# DragonBall.net
KiCad netlist of a schematic drawn in EAGLE
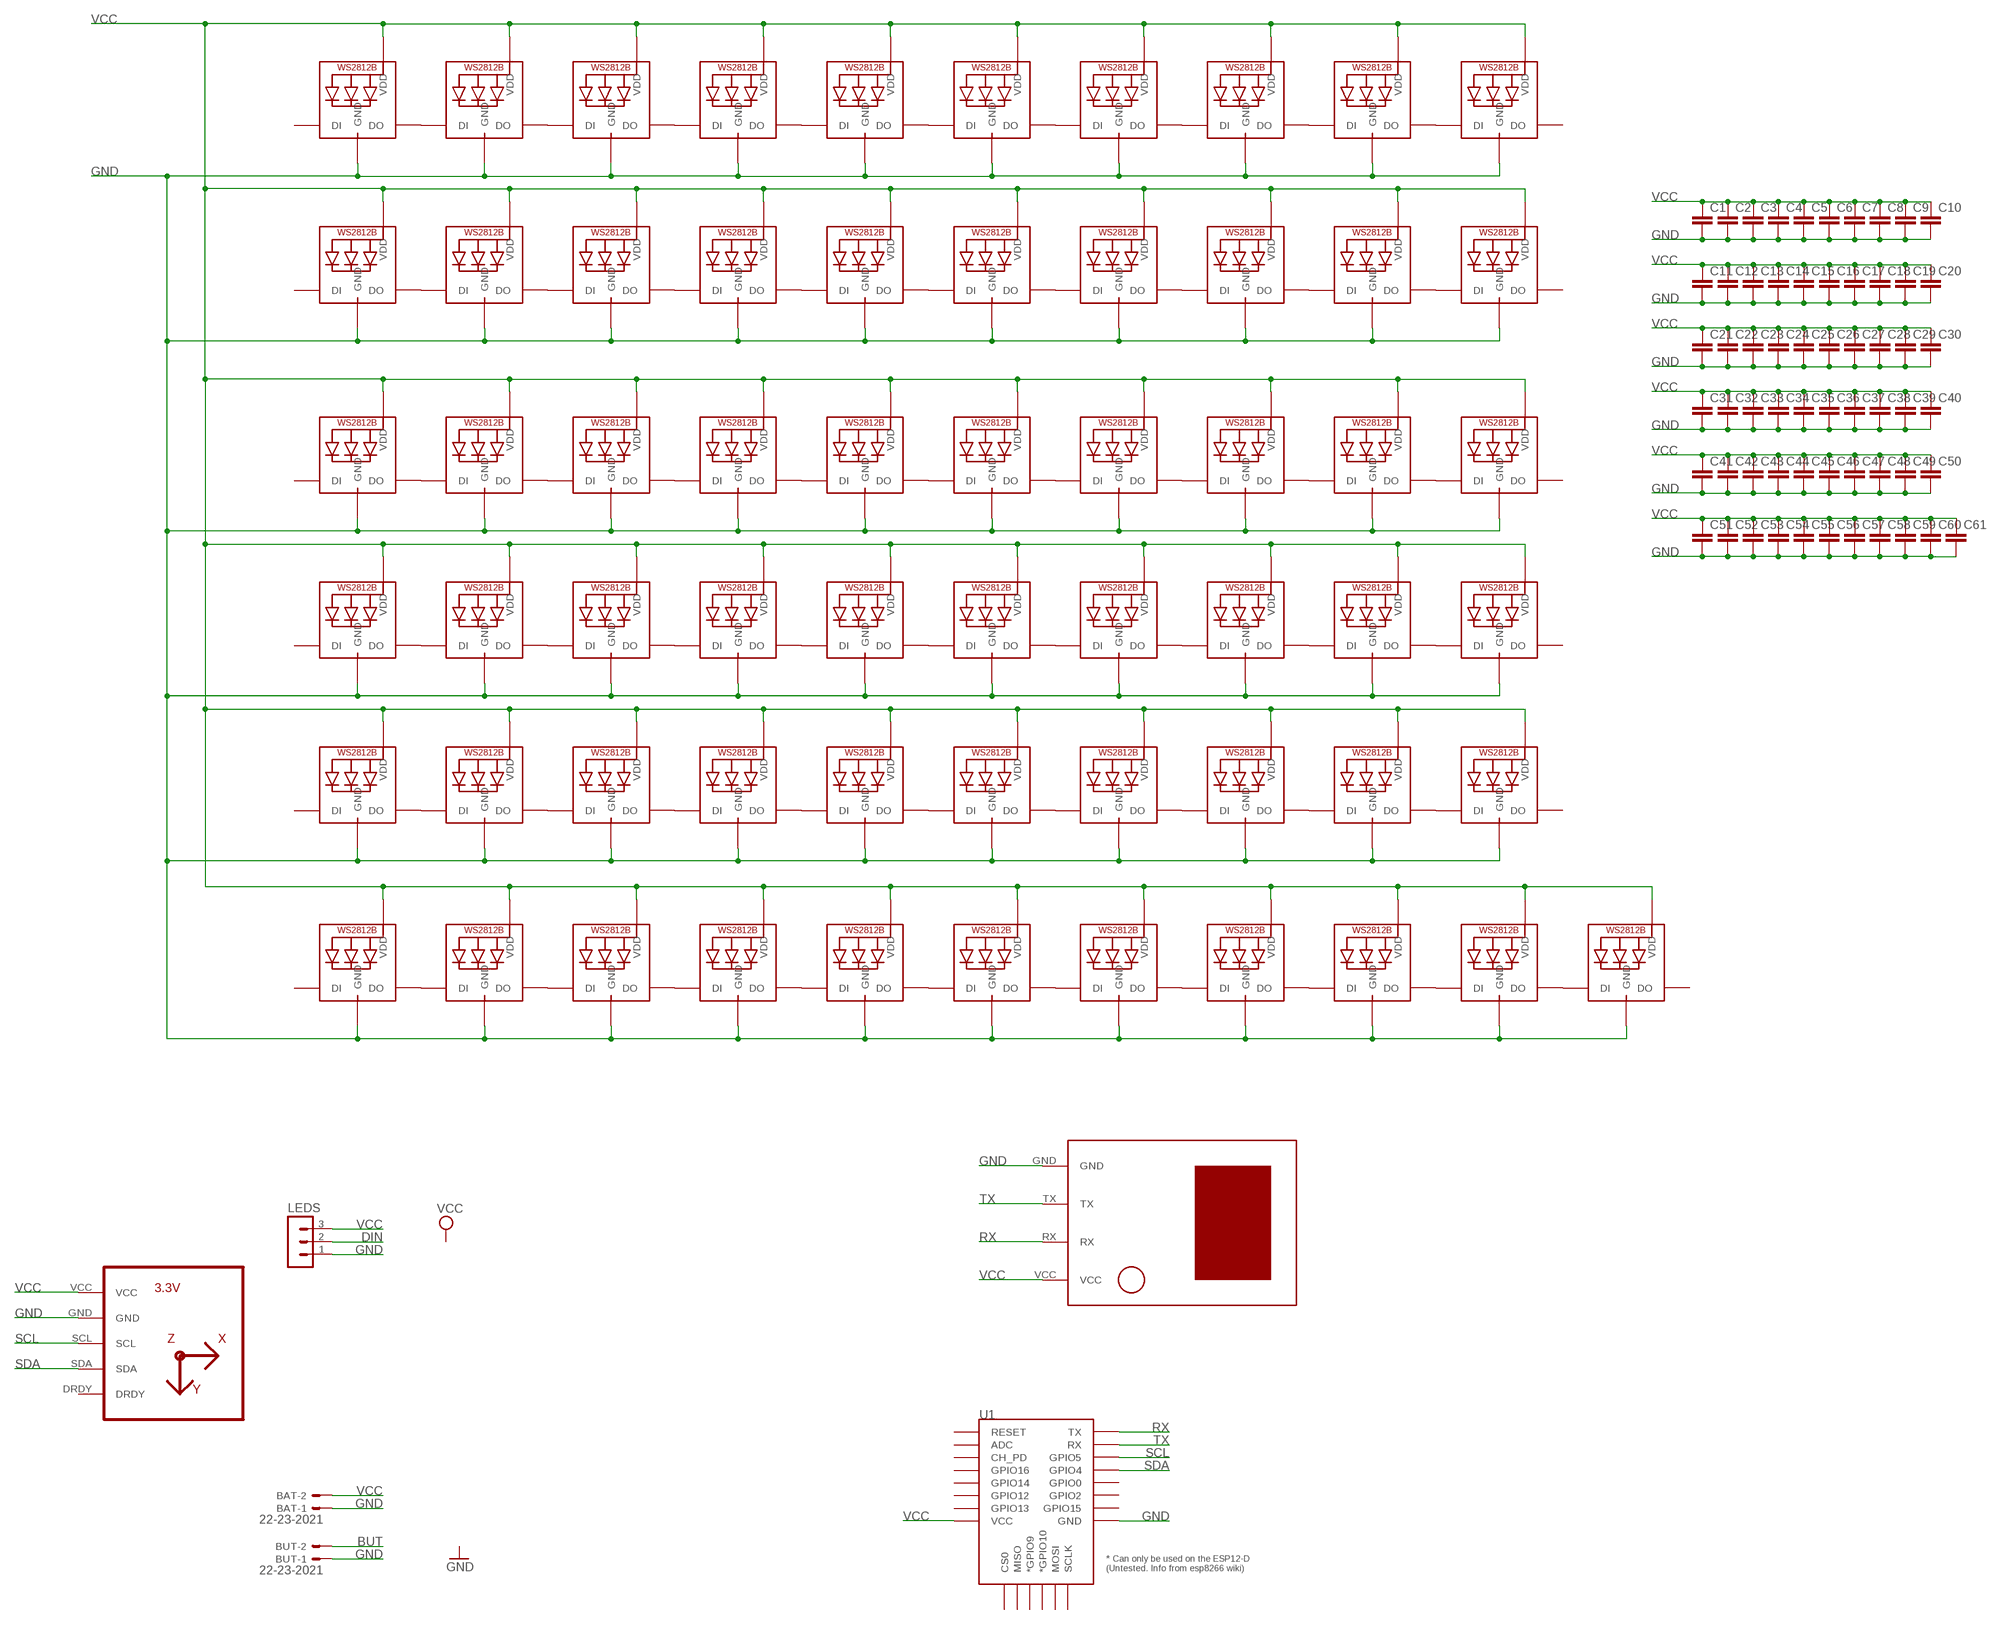
[diagram p0: schematic, sheet 1]

(export (version "E")
  (design (tool "Eeschema 10.0.6"))
  (components
    (comp (ref "BAT")
      (value "22-23-2021")
      (footprint "eagle-import:22-23-2021")
      (fields (field (name "MF") "MOLEX"))
      (libsource (lib "eagle-import") (part "22-23-2021"))
    )
    (comp (ref "BUT")
      (value "22-23-2021")
      (footprint "eagle-import:22-23-2021")
      (fields (field (name "MF") "MOLEX"))
      (libsource (lib "eagle-import") (part "22-23-2021"))
    )
    (comp (ref "C1")
      (value "C-EUC0402K")
      (footprint "eagle-import:C0402K")
      (libsource (lib "eagle-import") (part "C-EUC0402K"))
    )
    (comp (ref "C2")
      (value "C-EUC0402K")
      (footprint "eagle-import:C0402K")
      (libsource (lib "eagle-import") (part "C-EUC0402K"))
    )
    (comp (ref "C3")
      (value "C-EUC0402K")
      (footprint "eagle-import:C0402K")
      (libsource (lib "eagle-import") (part "C-EUC0402K"))
    )
    (comp (ref "C4")
      (value "C-EUC0402K")
      (footprint "eagle-import:C0402K")
      (libsource (lib "eagle-import") (part "C-EUC0402K"))
    )
    (comp (ref "C5")
      (value "C-EUC0402K")
      (footprint "eagle-import:C0402K")
      (libsource (lib "eagle-import") (part "C-EUC0402K"))
    )
    (comp (ref "C6")
      (value "C-EUC0402K")
      (footprint "eagle-import:C0402K")
      (libsource (lib "eagle-import") (part "C-EUC0402K"))
    )
    (comp (ref "C7")
      (value "C-EUC0402K")
      (footprint "eagle-import:C0402K")
      (libsource (lib "eagle-import") (part "C-EUC0402K"))
    )
    (comp (ref "C8")
      (value "C-EUC0402K")
      (footprint "eagle-import:C0402K")
      (libsource (lib "eagle-import") (part "C-EUC0402K"))
    )
    (comp (ref "C9")
      (value "C-EUC0402K")
      (footprint "eagle-import:C0402K")
      (libsource (lib "eagle-import") (part "C-EUC0402K"))
    )
    (comp (ref "C10")
      (value "C-EUC0402K")
      (footprint "eagle-import:C0402K")
      (libsource (lib "eagle-import") (part "C-EUC0402K"))
    )
    (comp (ref "C11")
      (value "C-EUC0402K")
      (footprint "eagle-import:C0402K")
      (libsource (lib "eagle-import") (part "C-EUC0402K"))
    )
    (comp (ref "C12")
      (value "C-EUC0402K")
      (footprint "eagle-import:C0402K")
      (libsource (lib "eagle-import") (part "C-EUC0402K"))
    )
    (comp (ref "C13")
      (value "C-EUC0402K")
      (footprint "eagle-import:C0402K")
      (libsource (lib "eagle-import") (part "C-EUC0402K"))
    )
    (comp (ref "C14")
      (value "C-EUC0402K")
      (footprint "eagle-import:C0402K")
      (libsource (lib "eagle-import") (part "C-EUC0402K"))
    )
    (comp (ref "C15")
      (value "C-EUC0402K")
      (footprint "eagle-import:C0402K")
      (libsource (lib "eagle-import") (part "C-EUC0402K"))
    )
    (comp (ref "C16")
      (value "C-EUC0402K")
      (footprint "eagle-import:C0402K")
      (libsource (lib "eagle-import") (part "C-EUC0402K"))
    )
    (comp (ref "C17")
      (value "C-EUC0402K")
      (footprint "eagle-import:C0402K")
      (libsource (lib "eagle-import") (part "C-EUC0402K"))
    )
    (comp (ref "C18")
      (value "C-EUC0402K")
      (footprint "eagle-import:C0402K")
      (libsource (lib "eagle-import") (part "C-EUC0402K"))
    )
    (comp (ref "C19")
      (value "C-EUC0402K")
      (footprint "eagle-import:C0402K")
      (libsource (lib "eagle-import") (part "C-EUC0402K"))
    )
    (comp (ref "C20")
      (value "C-EUC0402K")
      (footprint "eagle-import:C0402K")
      (libsource (lib "eagle-import") (part "C-EUC0402K"))
    )
    (comp (ref "C21")
      (value "C-EUC0402K")
      (footprint "eagle-import:C0402K")
      (libsource (lib "eagle-import") (part "C-EUC0402K"))
    )
    (comp (ref "C22")
      (value "C-EUC0402K")
      (footprint "eagle-import:C0402K")
      (libsource (lib "eagle-import") (part "C-EUC0402K"))
    )
    (comp (ref "C23")
      (value "C-EUC0402K")
      (footprint "eagle-import:C0402K")
      (libsource (lib "eagle-import") (part "C-EUC0402K"))
    )
    (comp (ref "C24")
      (value "C-EUC0402K")
      (footprint "eagle-import:C0402K")
      (libsource (lib "eagle-import") (part "C-EUC0402K"))
    )
    (comp (ref "C25")
      (value "C-EUC0402K")
      (footprint "eagle-import:C0402K")
      (libsource (lib "eagle-import") (part "C-EUC0402K"))
    )
    (comp (ref "C26")
      (value "C-EUC0402K")
      (footprint "eagle-import:C0402K")
      (libsource (lib "eagle-import") (part "C-EUC0402K"))
    )
    (comp (ref "C27")
      (value "C-EUC0402K")
      (footprint "eagle-import:C0402K")
      (libsource (lib "eagle-import") (part "C-EUC0402K"))
    )
    (comp (ref "C28")
      (value "C-EUC0402K")
      (footprint "eagle-import:C0402K")
      (libsource (lib "eagle-import") (part "C-EUC0402K"))
    )
    (comp (ref "C29")
      (value "C-EUC0402K")
      (footprint "eagle-import:C0402K")
      (libsource (lib "eagle-import") (part "C-EUC0402K"))
    )
    (comp (ref "C30")
      (value "C-EUC0402K")
      (footprint "eagle-import:C0402K")
      (libsource (lib "eagle-import") (part "C-EUC0402K"))
    )
    (comp (ref "C31")
      (value "C-EUC0402K")
      (footprint "eagle-import:C0402K")
      (libsource (lib "eagle-import") (part "C-EUC0402K"))
    )
    (comp (ref "C32")
      (value "C-EUC0402K")
      (footprint "eagle-import:C0402K")
      (libsource (lib "eagle-import") (part "C-EUC0402K"))
    )
    (comp (ref "C33")
      (value "C-EUC0402K")
      (footprint "eagle-import:C0402K")
      (libsource (lib "eagle-import") (part "C-EUC0402K"))
    )
    (comp (ref "C34")
      (value "C-EUC0402K")
      (footprint "eagle-import:C0402K")
      (libsource (lib "eagle-import") (part "C-EUC0402K"))
    )
    (comp (ref "C35")
      (value "C-EUC0402K")
      (footprint "eagle-import:C0402K")
      (libsource (lib "eagle-import") (part "C-EUC0402K"))
    )
    (comp (ref "C36")
      (value "C-EUC0402K")
      (footprint "eagle-import:C0402K")
      (libsource (lib "eagle-import") (part "C-EUC0402K"))
    )
    (comp (ref "C37")
      (value "C-EUC0402K")
      (footprint "eagle-import:C0402K")
      (libsource (lib "eagle-import") (part "C-EUC0402K"))
    )
    (comp (ref "C38")
      (value "C-EUC0402K")
      (footprint "eagle-import:C0402K")
      (libsource (lib "eagle-import") (part "C-EUC0402K"))
    )
    (comp (ref "C39")
      (value "C-EUC0402K")
      (footprint "eagle-import:C0402K")
      (libsource (lib "eagle-import") (part "C-EUC0402K"))
    )
    (comp (ref "C40")
      (value "C-EUC0402K")
      (footprint "eagle-import:C0402K")
      (libsource (lib "eagle-import") (part "C-EUC0402K"))
    )
    (comp (ref "C41")
      (value "C-EUC0402K")
      (footprint "eagle-import:C0402K")
      (libsource (lib "eagle-import") (part "C-EUC0402K"))
    )
    (comp (ref "C42")
      (value "C-EUC0402K")
      (footprint "eagle-import:C0402K")
      (libsource (lib "eagle-import") (part "C-EUC0402K"))
    )
    (comp (ref "C43")
      (value "C-EUC0402K")
      (footprint "eagle-import:C0402K")
      (libsource (lib "eagle-import") (part "C-EUC0402K"))
    )
    (comp (ref "C44")
      (value "C-EUC0402K")
      (footprint "eagle-import:C0402K")
      (libsource (lib "eagle-import") (part "C-EUC0402K"))
    )
    (comp (ref "C45")
      (value "C-EUC0402K")
      (footprint "eagle-import:C0402K")
      (libsource (lib "eagle-import") (part "C-EUC0402K"))
    )
    (comp (ref "C46")
      (value "C-EUC0402K")
      (footprint "eagle-import:C0402K")
      (libsource (lib "eagle-import") (part "C-EUC0402K"))
    )
    (comp (ref "C47")
      (value "C-EUC0402K")
      (footprint "eagle-import:C0402K")
      (libsource (lib "eagle-import") (part "C-EUC0402K"))
    )
    (comp (ref "C48")
      (value "C-EUC0402K")
      (footprint "eagle-import:C0402K")
      (libsource (lib "eagle-import") (part "C-EUC0402K"))
    )
    (comp (ref "C49")
      (value "C-EUC0402K")
      (footprint "eagle-import:C0402K")
      (libsource (lib "eagle-import") (part "C-EUC0402K"))
    )
    (comp (ref "C50")
      (value "C-EUC0402K")
      (footprint "eagle-import:C0402K")
      (libsource (lib "eagle-import") (part "C-EUC0402K"))
    )
    (comp (ref "C51")
      (value "C-EUC0402K")
      (footprint "eagle-import:C0402K")
      (libsource (lib "eagle-import") (part "C-EUC0402K"))
    )
    (comp (ref "C52")
      (value "C-EUC0402K")
      (footprint "eagle-import:C0402K")
      (libsource (lib "eagle-import") (part "C-EUC0402K"))
    )
    (comp (ref "C53")
      (value "C-EUC0402K")
      (footprint "eagle-import:C0402K")
      (libsource (lib "eagle-import") (part "C-EUC0402K"))
    )
    (comp (ref "C54")
      (value "C-EUC0402K")
      (footprint "eagle-import:C0402K")
      (libsource (lib "eagle-import") (part "C-EUC0402K"))
    )
    (comp (ref "C55")
      (value "C-EUC0402K")
      (footprint "eagle-import:C0402K")
      (libsource (lib "eagle-import") (part "C-EUC0402K"))
    )
    (comp (ref "C56")
      (value "C-EUC0402K")
      (footprint "eagle-import:C0402K")
      (libsource (lib "eagle-import") (part "C-EUC0402K"))
    )
    (comp (ref "C57")
      (value "C-EUC0402K")
      (footprint "eagle-import:C0402K")
      (libsource (lib "eagle-import") (part "C-EUC0402K"))
    )
    (comp (ref "C58")
      (value "C-EUC0402K")
      (footprint "eagle-import:C0402K")
      (libsource (lib "eagle-import") (part "C-EUC0402K"))
    )
    (comp (ref "C59")
      (value "C-EUC0402K")
      (footprint "eagle-import:C0402K")
      (libsource (lib "eagle-import") (part "C-EUC0402K"))
    )
    (comp (ref "C60")
      (value "C-EUC0402K")
      (footprint "eagle-import:C0402K")
      (libsource (lib "eagle-import") (part "C-EUC0402K"))
    )
    (comp (ref "C61")
      (value "C-EUC0402K")
      (footprint "eagle-import:C0402K")
      (libsource (lib "eagle-import") (part "C-EUC0402K"))
    )
    (comp (ref "GYRO")
      (value "HMC5883LGY-271")
      (footprint "eagle-import:GY-271")
      (libsource (lib "eagle-import") (part "HMC5883LGY-271"))
    )
    (comp (ref "LED1")
      (value "WS2812B_5050N")
      (footprint "eagle-import:WS2812B-NARROW")
      (libsource (lib "eagle-import") (part "WS2812B_5050N"))
    )
    (comp (ref "LED2")
      (value "WS2812B_5050N")
      (footprint "eagle-import:WS2812B-NARROW")
      (libsource (lib "eagle-import") (part "WS2812B_5050N"))
    )
    (comp (ref "LED3")
      (value "WS2812B_5050N")
      (footprint "eagle-import:WS2812B-NARROW")
      (libsource (lib "eagle-import") (part "WS2812B_5050N"))
    )
    (comp (ref "LED4")
      (value "WS2812B_5050N")
      (footprint "eagle-import:WS2812B-NARROW")
      (libsource (lib "eagle-import") (part "WS2812B_5050N"))
    )
    (comp (ref "LED5")
      (value "WS2812B_5050N")
      (footprint "eagle-import:WS2812B-NARROW")
      (libsource (lib "eagle-import") (part "WS2812B_5050N"))
    )
    (comp (ref "LED6")
      (value "WS2812B_5050N")
      (footprint "eagle-import:WS2812B-NARROW")
      (libsource (lib "eagle-import") (part "WS2812B_5050N"))
    )
    (comp (ref "LED7")
      (value "WS2812B_5050N")
      (footprint "eagle-import:WS2812B-NARROW")
      (libsource (lib "eagle-import") (part "WS2812B_5050N"))
    )
    (comp (ref "LED8")
      (value "WS2812B_5050N")
      (footprint "eagle-import:WS2812B-NARROW")
      (libsource (lib "eagle-import") (part "WS2812B_5050N"))
    )
    (comp (ref "LED9")
      (value "WS2812B_5050N")
      (footprint "eagle-import:WS2812B-NARROW")
      (libsource (lib "eagle-import") (part "WS2812B_5050N"))
    )
    (comp (ref "LED10")
      (value "WS2812B_5050N")
      (footprint "eagle-import:WS2812B-NARROW")
      (libsource (lib "eagle-import") (part "WS2812B_5050N"))
    )
    (comp (ref "LED11")
      (value "WS2812B_5050N")
      (footprint "eagle-import:WS2812B-NARROW")
      (libsource (lib "eagle-import") (part "WS2812B_5050N"))
    )
    (comp (ref "LED12")
      (value "WS2812B_5050N")
      (footprint "eagle-import:WS2812B-NARROW")
      (libsource (lib "eagle-import") (part "WS2812B_5050N"))
    )
    (comp (ref "LED13")
      (value "WS2812B_5050N")
      (footprint "eagle-import:WS2812B-NARROW")
      (libsource (lib "eagle-import") (part "WS2812B_5050N"))
    )
    (comp (ref "LED14")
      (value "WS2812B_5050N")
      (footprint "eagle-import:WS2812B-NARROW")
      (libsource (lib "eagle-import") (part "WS2812B_5050N"))
    )
    (comp (ref "LED15")
      (value "WS2812B_5050N")
      (footprint "eagle-import:WS2812B-NARROW")
      (libsource (lib "eagle-import") (part "WS2812B_5050N"))
    )
    (comp (ref "LED16")
      (value "WS2812B_5050N")
      (footprint "eagle-import:WS2812B-NARROW")
      (libsource (lib "eagle-import") (part "WS2812B_5050N"))
    )
    (comp (ref "LED17")
      (value "WS2812B_5050N")
      (footprint "eagle-import:WS2812B-NARROW")
      (libsource (lib "eagle-import") (part "WS2812B_5050N"))
    )
    (comp (ref "LED18")
      (value "WS2812B_5050N")
      (footprint "eagle-import:WS2812B-NARROW")
      (libsource (lib "eagle-import") (part "WS2812B_5050N"))
    )
    (comp (ref "LED19")
      (value "WS2812B_5050N")
      (footprint "eagle-import:WS2812B-NARROW")
      (libsource (lib "eagle-import") (part "WS2812B_5050N"))
    )
    (comp (ref "LED20")
      (value "WS2812B_5050N")
      (footprint "eagle-import:WS2812B-NARROW")
      (libsource (lib "eagle-import") (part "WS2812B_5050N"))
    )
    (comp (ref "LED21")
      (value "WS2812B_5050N")
      (footprint "eagle-import:WS2812B-NARROW")
      (libsource (lib "eagle-import") (part "WS2812B_5050N"))
    )
    (comp (ref "LED22")
      (value "WS2812B_5050N")
      (footprint "eagle-import:WS2812B-NARROW")
      (libsource (lib "eagle-import") (part "WS2812B_5050N"))
    )
    (comp (ref "LED23")
      (value "WS2812B_5050N")
      (footprint "eagle-import:WS2812B-NARROW")
      (libsource (lib "eagle-import") (part "WS2812B_5050N"))
    )
    (comp (ref "LED24")
      (value "WS2812B_5050N")
      (footprint "eagle-import:WS2812B-NARROW")
      (libsource (lib "eagle-import") (part "WS2812B_5050N"))
    )
    (comp (ref "LED25")
      (value "WS2812B_5050N")
      (footprint "eagle-import:WS2812B-NARROW")
      (libsource (lib "eagle-import") (part "WS2812B_5050N"))
    )
    (comp (ref "LED26")
      (value "WS2812B_5050N")
      (footprint "eagle-import:WS2812B-NARROW")
      (libsource (lib "eagle-import") (part "WS2812B_5050N"))
    )
    (comp (ref "LED27")
      (value "WS2812B_5050N")
      (footprint "eagle-import:WS2812B-NARROW")
      (libsource (lib "eagle-import") (part "WS2812B_5050N"))
    )
    (comp (ref "LED28")
      (value "WS2812B_5050N")
      (footprint "eagle-import:WS2812B-NARROW")
      (libsource (lib "eagle-import") (part "WS2812B_5050N"))
    )
    (comp (ref "LED29")
      (value "WS2812B_5050N")
      (footprint "eagle-import:WS2812B-NARROW")
      (libsource (lib "eagle-import") (part "WS2812B_5050N"))
    )
    (comp (ref "LED30")
      (value "WS2812B_5050N")
      (footprint "eagle-import:WS2812B-NARROW")
      (libsource (lib "eagle-import") (part "WS2812B_5050N"))
    )
    (comp (ref "LED31")
      (value "WS2812B_5050N")
      (footprint "eagle-import:WS2812B-NARROW")
      (libsource (lib "eagle-import") (part "WS2812B_5050N"))
    )
    (comp (ref "LED32")
      (value "WS2812B_5050N")
      (footprint "eagle-import:WS2812B-NARROW")
      (libsource (lib "eagle-import") (part "WS2812B_5050N"))
    )
    (comp (ref "LED33")
      (value "WS2812B_5050N")
      (footprint "eagle-import:WS2812B-NARROW")
      (libsource (lib "eagle-import") (part "WS2812B_5050N"))
    )
    (comp (ref "LED34")
      (value "WS2812B_5050N")
      (footprint "eagle-import:WS2812B-NARROW")
      (libsource (lib "eagle-import") (part "WS2812B_5050N"))
    )
    (comp (ref "LED35")
      (value "WS2812B_5050N")
      (footprint "eagle-import:WS2812B-NARROW")
      (libsource (lib "eagle-import") (part "WS2812B_5050N"))
    )
    (comp (ref "LED36")
      (value "WS2812B_5050N")
      (footprint "eagle-import:WS2812B-NARROW")
      (libsource (lib "eagle-import") (part "WS2812B_5050N"))
    )
    (comp (ref "LED37")
      (value "WS2812B_5050N")
      (footprint "eagle-import:WS2812B-NARROW")
      (libsource (lib "eagle-import") (part "WS2812B_5050N"))
    )
    (comp (ref "LED38")
      (value "WS2812B_5050N")
      (footprint "eagle-import:WS2812B-NARROW")
      (libsource (lib "eagle-import") (part "WS2812B_5050N"))
    )
    (comp (ref "LED39")
      (value "WS2812B_5050N")
      (footprint "eagle-import:WS2812B-NARROW")
      (libsource (lib "eagle-import") (part "WS2812B_5050N"))
    )
    (comp (ref "LED40")
      (value "WS2812B_5050N")
      (footprint "eagle-import:WS2812B-NARROW")
      (libsource (lib "eagle-import") (part "WS2812B_5050N"))
    )
    (comp (ref "LED41")
      (value "WS2812B_5050N")
      (footprint "eagle-import:WS2812B-NARROW")
      (libsource (lib "eagle-import") (part "WS2812B_5050N"))
    )
    (comp (ref "LED42")
      (value "WS2812B_5050N")
      (footprint "eagle-import:WS2812B-NARROW")
      (libsource (lib "eagle-import") (part "WS2812B_5050N"))
    )
    (comp (ref "LED43")
      (value "WS2812B_5050N")
      (footprint "eagle-import:WS2812B-NARROW")
      (libsource (lib "eagle-import") (part "WS2812B_5050N"))
    )
    (comp (ref "LED44")
      (value "WS2812B_5050N")
      (footprint "eagle-import:WS2812B-NARROW")
      (libsource (lib "eagle-import") (part "WS2812B_5050N"))
    )
    (comp (ref "LED45")
      (value "WS2812B_5050N")
      (footprint "eagle-import:WS2812B-NARROW")
      (libsource (lib "eagle-import") (part "WS2812B_5050N"))
    )
    (comp (ref "LED46")
      (value "WS2812B_5050N")
      (footprint "eagle-import:WS2812B-NARROW")
      (libsource (lib "eagle-import") (part "WS2812B_5050N"))
    )
    (comp (ref "LED47")
      (value "WS2812B_5050N")
      (footprint "eagle-import:WS2812B-NARROW")
      (libsource (lib "eagle-import") (part "WS2812B_5050N"))
    )
    (comp (ref "LED48")
      (value "WS2812B_5050N")
      (footprint "eagle-import:WS2812B-NARROW")
      (libsource (lib "eagle-import") (part "WS2812B_5050N"))
    )
    (comp (ref "LED49")
      (value "WS2812B_5050N")
      (footprint "eagle-import:WS2812B-NARROW")
      (libsource (lib "eagle-import") (part "WS2812B_5050N"))
    )
    (comp (ref "LED50")
      (value "WS2812B_5050N")
      (footprint "eagle-import:WS2812B-NARROW")
      (libsource (lib "eagle-import") (part "WS2812B_5050N"))
    )
    (comp (ref "LED51")
      (value "WS2812B_5050N")
      (footprint "eagle-import:WS2812B-NARROW")
      (libsource (lib "eagle-import") (part "WS2812B_5050N"))
    )
    (comp (ref "LED52")
      (value "WS2812B_5050N")
      (footprint "eagle-import:WS2812B-NARROW")
      (libsource (lib "eagle-import") (part "WS2812B_5050N"))
    )
    (comp (ref "LED53")
      (value "WS2812B_5050N")
      (footprint "eagle-import:WS2812B-NARROW")
      (libsource (lib "eagle-import") (part "WS2812B_5050N"))
    )
    (comp (ref "LED54")
      (value "WS2812B_5050N")
      (footprint "eagle-import:WS2812B-NARROW")
      (libsource (lib "eagle-import") (part "WS2812B_5050N"))
    )
    (comp (ref "LED55")
      (value "WS2812B_5050N")
      (footprint "eagle-import:WS2812B-NARROW")
      (libsource (lib "eagle-import") (part "WS2812B_5050N"))
    )
    (comp (ref "LED56")
      (value "WS2812B_5050N")
      (footprint "eagle-import:WS2812B-NARROW")
      (libsource (lib "eagle-import") (part "WS2812B_5050N"))
    )
    (comp (ref "LED57")
      (value "WS2812B_5050N")
      (footprint "eagle-import:WS2812B-NARROW")
      (libsource (lib "eagle-import") (part "WS2812B_5050N"))
    )
    (comp (ref "LED58")
      (value "WS2812B_5050N")
      (footprint "eagle-import:WS2812B-NARROW")
      (libsource (lib "eagle-import") (part "WS2812B_5050N"))
    )
    (comp (ref "LED59")
      (value "WS2812B_5050N")
      (footprint "eagle-import:WS2812B-NARROW")
      (libsource (lib "eagle-import") (part "WS2812B_5050N"))
    )
    (comp (ref "LED60")
      (value "WS2812B_5050N")
      (footprint "eagle-import:WS2812B-NARROW")
      (libsource (lib "eagle-import") (part "WS2812B_5050N"))
    )
    (comp (ref "LED61")
      (value "WS2812B_5050N")
      (footprint "eagle-import:WS2812B-NARROW")
      (libsource (lib "eagle-import") (part "WS2812B_5050N"))
    )
    (comp (ref "LEDS")
      (value "MA03-1")
      (footprint "eagle-import:MA03-1")
      (libsource (lib "eagle-import") (part "MA03-1"))
    )
    (comp (ref "U$3")
      (value "U-BLOX-NEO6V2")
      (footprint "eagle-import:U-BLOX-NEO6V2")
      (libsource (lib "eagle-import") (part "U-BLOX-NEO6V2"))
    )
    (comp (ref "U1")
      (value "ESP12ESMD")
      (footprint "eagle-import:ESP12E-SMD")
      (libsource (lib "eagle-import") (part "ESP12ESMD"))
    )
  )
  (nets
    (net (code "1") (name "/BUT") (class "Default")
      (node (ref "BUT") (pin "2") (pinfunction "S_2") (pintype "passive"))
    )
    (net (code "2") (name "/DIN") (class "Default")
      (node (ref "LEDS") (pin "2") (pinfunction "2_2") (pintype "passive"))
    )
    (net (code "3") (name "/RX") (class "Default")
      (node (ref "U$3") (pin "RX") (pinfunction "RX_RX") (pintype "bidirectional"))
      (node (ref "U1") (pin "TXD0") (pinfunction "TX_TXD0") (pintype "bidirectional"))
    )
    (net (code "4") (name "/SCL") (class "Default")
      (node (ref "GYRO") (pin "SCL") (pinfunction "SCL_SCL") (pintype "bidirectional"))
      (node (ref "U1") (pin "GPIO5") (pinfunction "GPIO5_GPIO5") (pintype "bidirectional"))
    )
    (net (code "5") (name "/SDA") (class "Default")
      (node (ref "GYRO") (pin "SDA") (pinfunction "SDA_SDA") (pintype "bidirectional"))
      (node (ref "U1") (pin "GPIO4") (pinfunction "GPIO4_GPIO4") (pintype "bidirectional"))
    )
    (net (code "6") (name "/TX") (class "Default")
      (node (ref "U$3") (pin "TX") (pinfunction "TX_TX") (pintype "bidirectional"))
      (node (ref "U1") (pin "RXD0") (pinfunction "RX_RXD0") (pintype "bidirectional"))
    )
    (net (code "7") (name "GND") (class "Default")
      (node (ref "BAT") (pin "1") (pinfunction "S_1") (pintype "passive"))
      (node (ref "BUT") (pin "1") (pinfunction "S_1") (pintype "passive"))
      (node (ref "C1") (pin "2") (pinfunction "2_2") (pintype "passive"))
      (node (ref "C10") (pin "2") (pinfunction "2_2") (pintype "passive"))
      (node (ref "C11") (pin "2") (pinfunction "2_2") (pintype "passive"))
      (node (ref "C12") (pin "2") (pinfunction "2_2") (pintype "passive"))
      (node (ref "C13") (pin "2") (pinfunction "2_2") (pintype "passive"))
      (node (ref "C14") (pin "2") (pinfunction "2_2") (pintype "passive"))
      (node (ref "C15") (pin "2") (pinfunction "2_2") (pintype "passive"))
      (node (ref "C16") (pin "2") (pinfunction "2_2") (pintype "passive"))
      (node (ref "C17") (pin "2") (pinfunction "2_2") (pintype "passive"))
      (node (ref "C18") (pin "2") (pinfunction "2_2") (pintype "passive"))
      (node (ref "C19") (pin "2") (pinfunction "2_2") (pintype "passive"))
      (node (ref "C2") (pin "2") (pinfunction "2_2") (pintype "passive"))
      (node (ref "C20") (pin "2") (pinfunction "2_2") (pintype "passive"))
      (node (ref "C21") (pin "2") (pinfunction "2_2") (pintype "passive"))
      (node (ref "C22") (pin "2") (pinfunction "2_2") (pintype "passive"))
      (node (ref "C23") (pin "2") (pinfunction "2_2") (pintype "passive"))
      (node (ref "C24") (pin "2") (pinfunction "2_2") (pintype "passive"))
      (node (ref "C25") (pin "2") (pinfunction "2_2") (pintype "passive"))
      (node (ref "C26") (pin "2") (pinfunction "2_2") (pintype "passive"))
      (node (ref "C27") (pin "2") (pinfunction "2_2") (pintype "passive"))
      (node (ref "C28") (pin "2") (pinfunction "2_2") (pintype "passive"))
      (node (ref "C29") (pin "2") (pinfunction "2_2") (pintype "passive"))
      (node (ref "C3") (pin "2") (pinfunction "2_2") (pintype "passive"))
      (node (ref "C30") (pin "2") (pinfunction "2_2") (pintype "passive"))
      (node (ref "C31") (pin "2") (pinfunction "2_2") (pintype "passive"))
      (node (ref "C32") (pin "2") (pinfunction "2_2") (pintype "passive"))
      (node (ref "C33") (pin "2") (pinfunction "2_2") (pintype "passive"))
      (node (ref "C34") (pin "2") (pinfunction "2_2") (pintype "passive"))
      (node (ref "C35") (pin "2") (pinfunction "2_2") (pintype "passive"))
      (node (ref "C36") (pin "2") (pinfunction "2_2") (pintype "passive"))
      (node (ref "C37") (pin "2") (pinfunction "2_2") (pintype "passive"))
      (node (ref "C38") (pin "2") (pinfunction "2_2") (pintype "passive"))
      (node (ref "C39") (pin "2") (pinfunction "2_2") (pintype "passive"))
      (node (ref "C4") (pin "2") (pinfunction "2_2") (pintype "passive"))
      (node (ref "C40") (pin "2") (pinfunction "2_2") (pintype "passive"))
      (node (ref "C41") (pin "2") (pinfunction "2_2") (pintype "passive"))
      (node (ref "C42") (pin "2") (pinfunction "2_2") (pintype "passive"))
      (node (ref "C43") (pin "2") (pinfunction "2_2") (pintype "passive"))
      (node (ref "C44") (pin "2") (pinfunction "2_2") (pintype "passive"))
      (node (ref "C45") (pin "2") (pinfunction "2_2") (pintype "passive"))
      (node (ref "C46") (pin "2") (pinfunction "2_2") (pintype "passive"))
      (node (ref "C47") (pin "2") (pinfunction "2_2") (pintype "passive"))
      (node (ref "C48") (pin "2") (pinfunction "2_2") (pintype "passive"))
      (node (ref "C49") (pin "2") (pinfunction "2_2") (pintype "passive"))
      (node (ref "C5") (pin "2") (pinfunction "2_2") (pintype "passive"))
      (node (ref "C50") (pin "2") (pinfunction "2_2") (pintype "passive"))
      (node (ref "C51") (pin "2") (pinfunction "2_2") (pintype "passive"))
      (node (ref "C52") (pin "2") (pinfunction "2_2") (pintype "passive"))
      (node (ref "C53") (pin "2") (pinfunction "2_2") (pintype "passive"))
      (node (ref "C54") (pin "2") (pinfunction "2_2") (pintype "passive"))
      (node (ref "C55") (pin "2") (pinfunction "2_2") (pintype "passive"))
      (node (ref "C56") (pin "2") (pinfunction "2_2") (pintype "passive"))
      (node (ref "C57") (pin "2") (pinfunction "2_2") (pintype "passive"))
      (node (ref "C58") (pin "2") (pinfunction "2_2") (pintype "passive"))
      (node (ref "C59") (pin "2") (pinfunction "2_2") (pintype "passive"))
      (node (ref "C6") (pin "2") (pinfunction "2_2") (pintype "passive"))
      (node (ref "C60") (pin "2") (pinfunction "2_2") (pintype "passive"))
      (node (ref "C61") (pin "2") (pinfunction "2_2") (pintype "passive"))
      (node (ref "C7") (pin "2") (pinfunction "2_2") (pintype "passive"))
      (node (ref "C8") (pin "2") (pinfunction "2_2") (pintype "passive"))
      (node (ref "C9") (pin "2") (pinfunction "2_2") (pintype "passive"))
      (node (ref "GYRO") (pin "GND") (pinfunction "GND_GND") (pintype "bidirectional"))
      (node (ref "LED1") (pin "3-GND") (pinfunction "GND_3-GND") (pintype "power_in"))
      (node (ref "LED10") (pin "3-GND") (pinfunction "GND_3-GND") (pintype "power_in"))
      (node (ref "LED11") (pin "3-GND") (pinfunction "GND_3-GND") (pintype "power_in"))
      (node (ref "LED12") (pin "3-GND") (pinfunction "GND_3-GND") (pintype "power_in"))
      (node (ref "LED13") (pin "3-GND") (pinfunction "GND_3-GND") (pintype "power_in"))
      (node (ref "LED14") (pin "3-GND") (pinfunction "GND_3-GND") (pintype "power_in"))
      (node (ref "LED15") (pin "3-GND") (pinfunction "GND_3-GND") (pintype "power_in"))
      (node (ref "LED16") (pin "3-GND") (pinfunction "GND_3-GND") (pintype "power_in"))
      (node (ref "LED17") (pin "3-GND") (pinfunction "GND_3-GND") (pintype "power_in"))
      (node (ref "LED18") (pin "3-GND") (pinfunction "GND_3-GND") (pintype "power_in"))
      (node (ref "LED19") (pin "3-GND") (pinfunction "GND_3-GND") (pintype "power_in"))
      (node (ref "LED2") (pin "3-GND") (pinfunction "GND_3-GND") (pintype "power_in"))
      (node (ref "LED20") (pin "3-GND") (pinfunction "GND_3-GND") (pintype "power_in"))
      (node (ref "LED21") (pin "3-GND") (pinfunction "GND_3-GND") (pintype "power_in"))
      (node (ref "LED22") (pin "3-GND") (pinfunction "GND_3-GND") (pintype "power_in"))
      (node (ref "LED23") (pin "3-GND") (pinfunction "GND_3-GND") (pintype "power_in"))
      (node (ref "LED24") (pin "3-GND") (pinfunction "GND_3-GND") (pintype "power_in"))
      (node (ref "LED25") (pin "3-GND") (pinfunction "GND_3-GND") (pintype "power_in"))
      (node (ref "LED26") (pin "3-GND") (pinfunction "GND_3-GND") (pintype "power_in"))
      (node (ref "LED27") (pin "3-GND") (pinfunction "GND_3-GND") (pintype "power_in"))
      (node (ref "LED28") (pin "3-GND") (pinfunction "GND_3-GND") (pintype "power_in"))
      (node (ref "LED29") (pin "3-GND") (pinfunction "GND_3-GND") (pintype "power_in"))
      (node (ref "LED3") (pin "3-GND") (pinfunction "GND_3-GND") (pintype "power_in"))
      (node (ref "LED30") (pin "3-GND") (pinfunction "GND_3-GND") (pintype "power_in"))
      (node (ref "LED31") (pin "3-GND") (pinfunction "GND_3-GND") (pintype "power_in"))
      (node (ref "LED32") (pin "3-GND") (pinfunction "GND_3-GND") (pintype "power_in"))
      (node (ref "LED33") (pin "3-GND") (pinfunction "GND_3-GND") (pintype "power_in"))
      (node (ref "LED34") (pin "3-GND") (pinfunction "GND_3-GND") (pintype "power_in"))
      (node (ref "LED35") (pin "3-GND") (pinfunction "GND_3-GND") (pintype "power_in"))
      (node (ref "LED36") (pin "3-GND") (pinfunction "GND_3-GND") (pintype "power_in"))
      (node (ref "LED37") (pin "3-GND") (pinfunction "GND_3-GND") (pintype "power_in"))
      (node (ref "LED38") (pin "3-GND") (pinfunction "GND_3-GND") (pintype "power_in"))
      (node (ref "LED39") (pin "3-GND") (pinfunction "GND_3-GND") (pintype "power_in"))
      (node (ref "LED4") (pin "3-GND") (pinfunction "GND_3-GND") (pintype "power_in"))
      (node (ref "LED40") (pin "3-GND") (pinfunction "GND_3-GND") (pintype "power_in"))
      (node (ref "LED41") (pin "3-GND") (pinfunction "GND_3-GND") (pintype "power_in"))
      (node (ref "LED42") (pin "3-GND") (pinfunction "GND_3-GND") (pintype "power_in"))
      (node (ref "LED43") (pin "3-GND") (pinfunction "GND_3-GND") (pintype "power_in"))
      (node (ref "LED44") (pin "3-GND") (pinfunction "GND_3-GND") (pintype "power_in"))
      (node (ref "LED45") (pin "3-GND") (pinfunction "GND_3-GND") (pintype "power_in"))
      (node (ref "LED46") (pin "3-GND") (pinfunction "GND_3-GND") (pintype "power_in"))
      (node (ref "LED47") (pin "3-GND") (pinfunction "GND_3-GND") (pintype "power_in"))
      (node (ref "LED48") (pin "3-GND") (pinfunction "GND_3-GND") (pintype "power_in"))
      (node (ref "LED49") (pin "3-GND") (pinfunction "GND_3-GND") (pintype "power_in"))
      (node (ref "LED5") (pin "3-GND") (pinfunction "GND_3-GND") (pintype "power_in"))
      (node (ref "LED50") (pin "3-GND") (pinfunction "GND_3-GND") (pintype "power_in"))
      (node (ref "LED51") (pin "3-GND") (pinfunction "GND_3-GND") (pintype "power_in"))
      (node (ref "LED52") (pin "3-GND") (pinfunction "GND_3-GND") (pintype "power_in"))
      (node (ref "LED53") (pin "3-GND") (pinfunction "GND_3-GND") (pintype "power_in"))
      (node (ref "LED54") (pin "3-GND") (pinfunction "GND_3-GND") (pintype "power_in"))
      (node (ref "LED55") (pin "3-GND") (pinfunction "GND_3-GND") (pintype "power_in"))
      (node (ref "LED56") (pin "3-GND") (pinfunction "GND_3-GND") (pintype "power_in"))
      (node (ref "LED57") (pin "3-GND") (pinfunction "GND_3-GND") (pintype "power_in"))
      (node (ref "LED58") (pin "3-GND") (pinfunction "GND_3-GND") (pintype "power_in"))
      (node (ref "LED59") (pin "3-GND") (pinfunction "GND_3-GND") (pintype "power_in"))
      (node (ref "LED6") (pin "3-GND") (pinfunction "GND_3-GND") (pintype "power_in"))
      (node (ref "LED60") (pin "3-GND") (pinfunction "GND_3-GND") (pintype "power_in"))
      (node (ref "LED61") (pin "3-GND") (pinfunction "GND_3-GND") (pintype "power_in"))
      (node (ref "LED7") (pin "3-GND") (pinfunction "GND_3-GND") (pintype "power_in"))
      (node (ref "LED8") (pin "3-GND") (pinfunction "GND_3-GND") (pintype "power_in"))
      (node (ref "LED9") (pin "3-GND") (pinfunction "GND_3-GND") (pintype "power_in"))
      (node (ref "LEDS") (pin "1") (pinfunction "1_1") (pintype "passive"))
      (node (ref "U$3") (pin "GND") (pinfunction "GND_GND") (pintype "bidirectional"))
      (node (ref "U1") (pin "GND") (pinfunction "GND_GND") (pintype "bidirectional"))
    )
    (net (code "8") (name "Net-(LED1-DO)") (class "Default")
      (node (ref "LED1") (pin "2-DOUT") (pinfunction "DO_2-DOUT") (pintype "output"))
      (node (ref "LED2") (pin "4-DIN") (pinfunction "DI_4-DIN") (pintype "input"))
    )
    (net (code "9") (name "Net-(LED2-DO)") (class "Default")
      (node (ref "LED2") (pin "2-DOUT") (pinfunction "DO_2-DOUT") (pintype "output"))
      (node (ref "LED3") (pin "4-DIN") (pinfunction "DI_4-DIN") (pintype "input"))
    )
    (net (code "10") (name "Net-(LED3-DO)") (class "Default")
      (node (ref "LED3") (pin "2-DOUT") (pinfunction "DO_2-DOUT") (pintype "output"))
      (node (ref "LED4") (pin "4-DIN") (pinfunction "DI_4-DIN") (pintype "input"))
    )
    (net (code "11") (name "Net-(LED4-DO)") (class "Default")
      (node (ref "LED4") (pin "2-DOUT") (pinfunction "DO_2-DOUT") (pintype "output"))
      (node (ref "LED5") (pin "4-DIN") (pinfunction "DI_4-DIN") (pintype "input"))
    )
    (net (code "12") (name "Net-(LED5-DO)") (class "Default")
      (node (ref "LED5") (pin "2-DOUT") (pinfunction "DO_2-DOUT") (pintype "output"))
      (node (ref "LED6") (pin "4-DIN") (pinfunction "DI_4-DIN") (pintype "input"))
    )
    (net (code "13") (name "Net-(LED6-DO)") (class "Default")
      (node (ref "LED6") (pin "2-DOUT") (pinfunction "DO_2-DOUT") (pintype "output"))
      (node (ref "LED7") (pin "4-DIN") (pinfunction "DI_4-DIN") (pintype "input"))
    )
    (net (code "14") (name "Net-(LED7-DO)") (class "Default")
      (node (ref "LED7") (pin "2-DOUT") (pinfunction "DO_2-DOUT") (pintype "output"))
      (node (ref "LED8") (pin "4-DIN") (pinfunction "DI_4-DIN") (pintype "input"))
    )
    (net (code "15") (name "Net-(LED8-DO)") (class "Default")
      (node (ref "LED8") (pin "2-DOUT") (pinfunction "DO_2-DOUT") (pintype "output"))
      (node (ref "LED9") (pin "4-DIN") (pinfunction "DI_4-DIN") (pintype "input"))
    )
    (net (code "16") (name "Net-(LED10-DI)") (class "Default")
      (node (ref "LED10") (pin "4-DIN") (pinfunction "DI_4-DIN") (pintype "input"))
      (node (ref "LED9") (pin "2-DOUT") (pinfunction "DO_2-DOUT") (pintype "output"))
    )
    (net (code "17") (name "Net-(LED11-DO)") (class "Default")
      (node (ref "LED11") (pin "2-DOUT") (pinfunction "DO_2-DOUT") (pintype "output"))
      (node (ref "LED12") (pin "4-DIN") (pinfunction "DI_4-DIN") (pintype "input"))
    )
    (net (code "18") (name "Net-(LED12-DO)") (class "Default")
      (node (ref "LED12") (pin "2-DOUT") (pinfunction "DO_2-DOUT") (pintype "output"))
      (node (ref "LED13") (pin "4-DIN") (pinfunction "DI_4-DIN") (pintype "input"))
    )
    (net (code "19") (name "Net-(LED13-DO)") (class "Default")
      (node (ref "LED13") (pin "2-DOUT") (pinfunction "DO_2-DOUT") (pintype "output"))
      (node (ref "LED14") (pin "4-DIN") (pinfunction "DI_4-DIN") (pintype "input"))
    )
    (net (code "20") (name "Net-(LED14-DO)") (class "Default")
      (node (ref "LED14") (pin "2-DOUT") (pinfunction "DO_2-DOUT") (pintype "output"))
      (node (ref "LED15") (pin "4-DIN") (pinfunction "DI_4-DIN") (pintype "input"))
    )
    (net (code "21") (name "Net-(LED15-DO)") (class "Default")
      (node (ref "LED15") (pin "2-DOUT") (pinfunction "DO_2-DOUT") (pintype "output"))
      (node (ref "LED16") (pin "4-DIN") (pinfunction "DI_4-DIN") (pintype "input"))
    )
    (net (code "22") (name "Net-(LED16-DO)") (class "Default")
      (node (ref "LED16") (pin "2-DOUT") (pinfunction "DO_2-DOUT") (pintype "output"))
      (node (ref "LED17") (pin "4-DIN") (pinfunction "DI_4-DIN") (pintype "input"))
    )
    (net (code "23") (name "Net-(LED17-DO)") (class "Default")
      (node (ref "LED17") (pin "2-DOUT") (pinfunction "DO_2-DOUT") (pintype "output"))
      (node (ref "LED18") (pin "4-DIN") (pinfunction "DI_4-DIN") (pintype "input"))
    )
    (net (code "24") (name "Net-(LED18-DO)") (class "Default")
      (node (ref "LED18") (pin "2-DOUT") (pinfunction "DO_2-DOUT") (pintype "output"))
      (node (ref "LED19") (pin "4-DIN") (pinfunction "DI_4-DIN") (pintype "input"))
    )
    (net (code "25") (name "Net-(LED19-DO)") (class "Default")
      (node (ref "LED19") (pin "2-DOUT") (pinfunction "DO_2-DOUT") (pintype "output"))
      (node (ref "LED20") (pin "4-DIN") (pinfunction "DI_4-DIN") (pintype "input"))
    )
    (net (code "26") (name "Net-(LED21-DO)") (class "Default")
      (node (ref "LED21") (pin "2-DOUT") (pinfunction "DO_2-DOUT") (pintype "output"))
      (node (ref "LED22") (pin "4-DIN") (pinfunction "DI_4-DIN") (pintype "input"))
    )
    (net (code "27") (name "Net-(LED22-DO)") (class "Default")
      (node (ref "LED22") (pin "2-DOUT") (pinfunction "DO_2-DOUT") (pintype "output"))
      (node (ref "LED23") (pin "4-DIN") (pinfunction "DI_4-DIN") (pintype "input"))
    )
    (net (code "28") (name "Net-(LED23-DO)") (class "Default")
      (node (ref "LED23") (pin "2-DOUT") (pinfunction "DO_2-DOUT") (pintype "output"))
      (node (ref "LED24") (pin "4-DIN") (pinfunction "DI_4-DIN") (pintype "input"))
    )
    (net (code "29") (name "Net-(LED24-DO)") (class "Default")
      (node (ref "LED24") (pin "2-DOUT") (pinfunction "DO_2-DOUT") (pintype "output"))
      (node (ref "LED25") (pin "4-DIN") (pinfunction "DI_4-DIN") (pintype "input"))
    )
    (net (code "30") (name "Net-(LED25-DO)") (class "Default")
      (node (ref "LED25") (pin "2-DOUT") (pinfunction "DO_2-DOUT") (pintype "output"))
      (node (ref "LED26") (pin "4-DIN") (pinfunction "DI_4-DIN") (pintype "input"))
    )
    (net (code "31") (name "Net-(LED26-DO)") (class "Default")
      (node (ref "LED26") (pin "2-DOUT") (pinfunction "DO_2-DOUT") (pintype "output"))
      (node (ref "LED27") (pin "4-DIN") (pinfunction "DI_4-DIN") (pintype "input"))
    )
    (net (code "32") (name "Net-(LED27-DO)") (class "Default")
      (node (ref "LED27") (pin "2-DOUT") (pinfunction "DO_2-DOUT") (pintype "output"))
      (node (ref "LED28") (pin "4-DIN") (pinfunction "DI_4-DIN") (pintype "input"))
    )
    (net (code "33") (name "Net-(LED28-DO)") (class "Default")
      (node (ref "LED28") (pin "2-DOUT") (pinfunction "DO_2-DOUT") (pintype "output"))
      (node (ref "LED29") (pin "4-DIN") (pinfunction "DI_4-DIN") (pintype "input"))
    )
    (net (code "34") (name "Net-(LED29-DO)") (class "Default")
      (node (ref "LED29") (pin "2-DOUT") (pinfunction "DO_2-DOUT") (pintype "output"))
      (node (ref "LED30") (pin "4-DIN") (pinfunction "DI_4-DIN") (pintype "input"))
    )
    (net (code "35") (name "Net-(LED31-DO)") (class "Default")
      (node (ref "LED31") (pin "2-DOUT") (pinfunction "DO_2-DOUT") (pintype "output"))
      (node (ref "LED32") (pin "4-DIN") (pinfunction "DI_4-DIN") (pintype "input"))
    )
    (net (code "36") (name "Net-(LED32-DO)") (class "Default")
      (node (ref "LED32") (pin "2-DOUT") (pinfunction "DO_2-DOUT") (pintype "output"))
      (node (ref "LED33") (pin "4-DIN") (pinfunction "DI_4-DIN") (pintype "input"))
    )
    (net (code "37") (name "Net-(LED33-DO)") (class "Default")
      (node (ref "LED33") (pin "2-DOUT") (pinfunction "DO_2-DOUT") (pintype "output"))
      (node (ref "LED34") (pin "4-DIN") (pinfunction "DI_4-DIN") (pintype "input"))
    )
    (net (code "38") (name "Net-(LED34-DO)") (class "Default")
      (node (ref "LED34") (pin "2-DOUT") (pinfunction "DO_2-DOUT") (pintype "output"))
      (node (ref "LED35") (pin "4-DIN") (pinfunction "DI_4-DIN") (pintype "input"))
    )
    (net (code "39") (name "Net-(LED35-DO)") (class "Default")
      (node (ref "LED35") (pin "2-DOUT") (pinfunction "DO_2-DOUT") (pintype "output"))
      (node (ref "LED36") (pin "4-DIN") (pinfunction "DI_4-DIN") (pintype "input"))
    )
    (net (code "40") (name "Net-(LED36-DO)") (class "Default")
      (node (ref "LED36") (pin "2-DOUT") (pinfunction "DO_2-DOUT") (pintype "output"))
      (node (ref "LED37") (pin "4-DIN") (pinfunction "DI_4-DIN") (pintype "input"))
    )
    (net (code "41") (name "Net-(LED37-DO)") (class "Default")
      (node (ref "LED37") (pin "2-DOUT") (pinfunction "DO_2-DOUT") (pintype "output"))
      (node (ref "LED38") (pin "4-DIN") (pinfunction "DI_4-DIN") (pintype "input"))
    )
    (net (code "42") (name "Net-(LED38-DO)") (class "Default")
      (node (ref "LED38") (pin "2-DOUT") (pinfunction "DO_2-DOUT") (pintype "output"))
      (node (ref "LED39") (pin "4-DIN") (pinfunction "DI_4-DIN") (pintype "input"))
    )
    (net (code "43") (name "Net-(LED39-DO)") (class "Default")
      (node (ref "LED39") (pin "2-DOUT") (pinfunction "DO_2-DOUT") (pintype "output"))
      (node (ref "LED40") (pin "4-DIN") (pinfunction "DI_4-DIN") (pintype "input"))
    )
    (net (code "44") (name "Net-(LED41-DO)") (class "Default")
      (node (ref "LED41") (pin "2-DOUT") (pinfunction "DO_2-DOUT") (pintype "output"))
      (node (ref "LED42") (pin "4-DIN") (pinfunction "DI_4-DIN") (pintype "input"))
    )
    (net (code "45") (name "Net-(LED42-DO)") (class "Default")
      (node (ref "LED42") (pin "2-DOUT") (pinfunction "DO_2-DOUT") (pintype "output"))
      (node (ref "LED43") (pin "4-DIN") (pinfunction "DI_4-DIN") (pintype "input"))
    )
    (net (code "46") (name "Net-(LED43-DO)") (class "Default")
      (node (ref "LED43") (pin "2-DOUT") (pinfunction "DO_2-DOUT") (pintype "output"))
      (node (ref "LED44") (pin "4-DIN") (pinfunction "DI_4-DIN") (pintype "input"))
    )
    (net (code "47") (name "Net-(LED44-DO)") (class "Default")
      (node (ref "LED44") (pin "2-DOUT") (pinfunction "DO_2-DOUT") (pintype "output"))
      (node (ref "LED45") (pin "4-DIN") (pinfunction "DI_4-DIN") (pintype "input"))
    )
    (net (code "48") (name "Net-(LED45-DO)") (class "Default")
      (node (ref "LED45") (pin "2-DOUT") (pinfunction "DO_2-DOUT") (pintype "output"))
      (node (ref "LED46") (pin "4-DIN") (pinfunction "DI_4-DIN") (pintype "input"))
    )
    (net (code "49") (name "Net-(LED46-DO)") (class "Default")
      (node (ref "LED46") (pin "2-DOUT") (pinfunction "DO_2-DOUT") (pintype "output"))
      (node (ref "LED47") (pin "4-DIN") (pinfunction "DI_4-DIN") (pintype "input"))
    )
    (net (code "50") (name "Net-(LED47-DO)") (class "Default")
      (node (ref "LED47") (pin "2-DOUT") (pinfunction "DO_2-DOUT") (pintype "output"))
      (node (ref "LED48") (pin "4-DIN") (pinfunction "DI_4-DIN") (pintype "input"))
    )
    (net (code "51") (name "Net-(LED48-DO)") (class "Default")
      (node (ref "LED48") (pin "2-DOUT") (pinfunction "DO_2-DOUT") (pintype "output"))
      (node (ref "LED49") (pin "4-DIN") (pinfunction "DI_4-DIN") (pintype "input"))
    )
    (net (code "52") (name "Net-(LED49-DO)") (class "Default")
      (node (ref "LED49") (pin "2-DOUT") (pinfunction "DO_2-DOUT") (pintype "output"))
      (node (ref "LED50") (pin "4-DIN") (pinfunction "DI_4-DIN") (pintype "input"))
    )
    (net (code "53") (name "Net-(LED51-DO)") (class "Default")
      (node (ref "LED51") (pin "2-DOUT") (pinfunction "DO_2-DOUT") (pintype "output"))
      (node (ref "LED52") (pin "4-DIN") (pinfunction "DI_4-DIN") (pintype "input"))
    )
    (net (code "54") (name "Net-(LED52-DO)") (class "Default")
      (node (ref "LED52") (pin "2-DOUT") (pinfunction "DO_2-DOUT") (pintype "output"))
      (node (ref "LED53") (pin "4-DIN") (pinfunction "DI_4-DIN") (pintype "input"))
    )
    (net (code "55") (name "Net-(LED53-DO)") (class "Default")
      (node (ref "LED53") (pin "2-DOUT") (pinfunction "DO_2-DOUT") (pintype "output"))
      (node (ref "LED54") (pin "4-DIN") (pinfunction "DI_4-DIN") (pintype "input"))
    )
    (net (code "56") (name "Net-(LED54-DO)") (class "Default")
      (node (ref "LED54") (pin "2-DOUT") (pinfunction "DO_2-DOUT") (pintype "output"))
      (node (ref "LED55") (pin "4-DIN") (pinfunction "DI_4-DIN") (pintype "input"))
    )
    (net (code "57") (name "Net-(LED55-DO)") (class "Default")
      (node (ref "LED55") (pin "2-DOUT") (pinfunction "DO_2-DOUT") (pintype "output"))
      (node (ref "LED56") (pin "4-DIN") (pinfunction "DI_4-DIN") (pintype "input"))
    )
    (net (code "58") (name "Net-(LED56-DO)") (class "Default")
      (node (ref "LED56") (pin "2-DOUT") (pinfunction "DO_2-DOUT") (pintype "output"))
      (node (ref "LED57") (pin "4-DIN") (pinfunction "DI_4-DIN") (pintype "input"))
    )
    (net (code "59") (name "Net-(LED57-DO)") (class "Default")
      (node (ref "LED57") (pin "2-DOUT") (pinfunction "DO_2-DOUT") (pintype "output"))
      (node (ref "LED58") (pin "4-DIN") (pinfunction "DI_4-DIN") (pintype "input"))
    )
    (net (code "60") (name "Net-(LED58-DO)") (class "Default")
      (node (ref "LED58") (pin "2-DOUT") (pinfunction "DO_2-DOUT") (pintype "output"))
      (node (ref "LED59") (pin "4-DIN") (pinfunction "DI_4-DIN") (pintype "input"))
    )
    (net (code "61") (name "Net-(LED59-DO)") (class "Default")
      (node (ref "LED59") (pin "2-DOUT") (pinfunction "DO_2-DOUT") (pintype "output"))
      (node (ref "LED60") (pin "4-DIN") (pinfunction "DI_4-DIN") (pintype "input"))
    )
    (net (code "62") (name "Net-(LED60-DO)") (class "Default")
      (node (ref "LED60") (pin "2-DOUT") (pinfunction "DO_2-DOUT") (pintype "output"))
      (node (ref "LED61") (pin "4-DIN") (pinfunction "DI_4-DIN") (pintype "input"))
    )
    (net (code "63") (name "VCC") (class "Default")
      (node (ref "BAT") (pin "2") (pinfunction "S_2") (pintype "passive"))
      (node (ref "C1") (pin "1") (pinfunction "1_1") (pintype "passive"))
      (node (ref "C10") (pin "1") (pinfunction "1_1") (pintype "passive"))
      (node (ref "C11") (pin "1") (pinfunction "1_1") (pintype "passive"))
      (node (ref "C12") (pin "1") (pinfunction "1_1") (pintype "passive"))
      (node (ref "C13") (pin "1") (pinfunction "1_1") (pintype "passive"))
      (node (ref "C14") (pin "1") (pinfunction "1_1") (pintype "passive"))
      (node (ref "C15") (pin "1") (pinfunction "1_1") (pintype "passive"))
      (node (ref "C16") (pin "1") (pinfunction "1_1") (pintype "passive"))
      (node (ref "C17") (pin "1") (pinfunction "1_1") (pintype "passive"))
      (node (ref "C18") (pin "1") (pinfunction "1_1") (pintype "passive"))
      (node (ref "C19") (pin "1") (pinfunction "1_1") (pintype "passive"))
      (node (ref "C2") (pin "1") (pinfunction "1_1") (pintype "passive"))
      (node (ref "C20") (pin "1") (pinfunction "1_1") (pintype "passive"))
      (node (ref "C21") (pin "1") (pinfunction "1_1") (pintype "passive"))
      (node (ref "C22") (pin "1") (pinfunction "1_1") (pintype "passive"))
      (node (ref "C23") (pin "1") (pinfunction "1_1") (pintype "passive"))
      (node (ref "C24") (pin "1") (pinfunction "1_1") (pintype "passive"))
      (node (ref "C25") (pin "1") (pinfunction "1_1") (pintype "passive"))
      (node (ref "C26") (pin "1") (pinfunction "1_1") (pintype "passive"))
      (node (ref "C27") (pin "1") (pinfunction "1_1") (pintype "passive"))
      (node (ref "C28") (pin "1") (pinfunction "1_1") (pintype "passive"))
      (node (ref "C29") (pin "1") (pinfunction "1_1") (pintype "passive"))
      (node (ref "C3") (pin "1") (pinfunction "1_1") (pintype "passive"))
      (node (ref "C30") (pin "1") (pinfunction "1_1") (pintype "passive"))
      (node (ref "C31") (pin "1") (pinfunction "1_1") (pintype "passive"))
      (node (ref "C32") (pin "1") (pinfunction "1_1") (pintype "passive"))
      (node (ref "C33") (pin "1") (pinfunction "1_1") (pintype "passive"))
      (node (ref "C34") (pin "1") (pinfunction "1_1") (pintype "passive"))
      (node (ref "C35") (pin "1") (pinfunction "1_1") (pintype "passive"))
      (node (ref "C36") (pin "1") (pinfunction "1_1") (pintype "passive"))
      (node (ref "C37") (pin "1") (pinfunction "1_1") (pintype "passive"))
      (node (ref "C38") (pin "1") (pinfunction "1_1") (pintype "passive"))
      (node (ref "C39") (pin "1") (pinfunction "1_1") (pintype "passive"))
      (node (ref "C4") (pin "1") (pinfunction "1_1") (pintype "passive"))
      (node (ref "C40") (pin "1") (pinfunction "1_1") (pintype "passive"))
      (node (ref "C41") (pin "1") (pinfunction "1_1") (pintype "passive"))
      (node (ref "C42") (pin "1") (pinfunction "1_1") (pintype "passive"))
      (node (ref "C43") (pin "1") (pinfunction "1_1") (pintype "passive"))
      (node (ref "C44") (pin "1") (pinfunction "1_1") (pintype "passive"))
      (node (ref "C45") (pin "1") (pinfunction "1_1") (pintype "passive"))
      (node (ref "C46") (pin "1") (pinfunction "1_1") (pintype "passive"))
      (node (ref "C47") (pin "1") (pinfunction "1_1") (pintype "passive"))
      (node (ref "C48") (pin "1") (pinfunction "1_1") (pintype "passive"))
      (node (ref "C49") (pin "1") (pinfunction "1_1") (pintype "passive"))
      (node (ref "C5") (pin "1") (pinfunction "1_1") (pintype "passive"))
      (node (ref "C50") (pin "1") (pinfunction "1_1") (pintype "passive"))
      (node (ref "C51") (pin "1") (pinfunction "1_1") (pintype "passive"))
      (node (ref "C52") (pin "1") (pinfunction "1_1") (pintype "passive"))
      (node (ref "C53") (pin "1") (pinfunction "1_1") (pintype "passive"))
      (node (ref "C54") (pin "1") (pinfunction "1_1") (pintype "passive"))
      (node (ref "C55") (pin "1") (pinfunction "1_1") (pintype "passive"))
      (node (ref "C56") (pin "1") (pinfunction "1_1") (pintype "passive"))
      (node (ref "C57") (pin "1") (pinfunction "1_1") (pintype "passive"))
      (node (ref "C58") (pin "1") (pinfunction "1_1") (pintype "passive"))
      (node (ref "C59") (pin "1") (pinfunction "1_1") (pintype "passive"))
      (node (ref "C6") (pin "1") (pinfunction "1_1") (pintype "passive"))
      (node (ref "C60") (pin "1") (pinfunction "1_1") (pintype "passive"))
      (node (ref "C61") (pin "1") (pinfunction "1_1") (pintype "passive"))
      (node (ref "C7") (pin "1") (pinfunction "1_1") (pintype "passive"))
      (node (ref "C8") (pin "1") (pinfunction "1_1") (pintype "passive"))
      (node (ref "C9") (pin "1") (pinfunction "1_1") (pintype "passive"))
      (node (ref "GYRO") (pin "VCC") (pinfunction "VCC_VCC") (pintype "bidirectional"))
      (node (ref "LED1") (pin "1-VDD") (pinfunction "VDD_1-VDD") (pintype "power_in"))
      (node (ref "LED10") (pin "1-VDD") (pinfunction "VDD_1-VDD") (pintype "power_in"))
      (node (ref "LED11") (pin "1-VDD") (pinfunction "VDD_1-VDD") (pintype "power_in"))
      (node (ref "LED12") (pin "1-VDD") (pinfunction "VDD_1-VDD") (pintype "power_in"))
      (node (ref "LED13") (pin "1-VDD") (pinfunction "VDD_1-VDD") (pintype "power_in"))
      (node (ref "LED14") (pin "1-VDD") (pinfunction "VDD_1-VDD") (pintype "power_in"))
      (node (ref "LED15") (pin "1-VDD") (pinfunction "VDD_1-VDD") (pintype "power_in"))
      (node (ref "LED16") (pin "1-VDD") (pinfunction "VDD_1-VDD") (pintype "power_in"))
      (node (ref "LED17") (pin "1-VDD") (pinfunction "VDD_1-VDD") (pintype "power_in"))
      (node (ref "LED18") (pin "1-VDD") (pinfunction "VDD_1-VDD") (pintype "power_in"))
      (node (ref "LED19") (pin "1-VDD") (pinfunction "VDD_1-VDD") (pintype "power_in"))
      (node (ref "LED2") (pin "1-VDD") (pinfunction "VDD_1-VDD") (pintype "power_in"))
      (node (ref "LED20") (pin "1-VDD") (pinfunction "VDD_1-VDD") (pintype "power_in"))
      (node (ref "LED21") (pin "1-VDD") (pinfunction "VDD_1-VDD") (pintype "power_in"))
      (node (ref "LED22") (pin "1-VDD") (pinfunction "VDD_1-VDD") (pintype "power_in"))
      (node (ref "LED23") (pin "1-VDD") (pinfunction "VDD_1-VDD") (pintype "power_in"))
      (node (ref "LED24") (pin "1-VDD") (pinfunction "VDD_1-VDD") (pintype "power_in"))
      (node (ref "LED25") (pin "1-VDD") (pinfunction "VDD_1-VDD") (pintype "power_in"))
      (node (ref "LED26") (pin "1-VDD") (pinfunction "VDD_1-VDD") (pintype "power_in"))
      (node (ref "LED27") (pin "1-VDD") (pinfunction "VDD_1-VDD") (pintype "power_in"))
      (node (ref "LED28") (pin "1-VDD") (pinfunction "VDD_1-VDD") (pintype "power_in"))
      (node (ref "LED29") (pin "1-VDD") (pinfunction "VDD_1-VDD") (pintype "power_in"))
      (node (ref "LED3") (pin "1-VDD") (pinfunction "VDD_1-VDD") (pintype "power_in"))
      (node (ref "LED30") (pin "1-VDD") (pinfunction "VDD_1-VDD") (pintype "power_in"))
      (node (ref "LED31") (pin "1-VDD") (pinfunction "VDD_1-VDD") (pintype "power_in"))
      (node (ref "LED32") (pin "1-VDD") (pinfunction "VDD_1-VDD") (pintype "power_in"))
      (node (ref "LED33") (pin "1-VDD") (pinfunction "VDD_1-VDD") (pintype "power_in"))
      (node (ref "LED34") (pin "1-VDD") (pinfunction "VDD_1-VDD") (pintype "power_in"))
      (node (ref "LED35") (pin "1-VDD") (pinfunction "VDD_1-VDD") (pintype "power_in"))
      (node (ref "LED36") (pin "1-VDD") (pinfunction "VDD_1-VDD") (pintype "power_in"))
      (node (ref "LED37") (pin "1-VDD") (pinfunction "VDD_1-VDD") (pintype "power_in"))
      (node (ref "LED38") (pin "1-VDD") (pinfunction "VDD_1-VDD") (pintype "power_in"))
      (node (ref "LED39") (pin "1-VDD") (pinfunction "VDD_1-VDD") (pintype "power_in"))
      (node (ref "LED4") (pin "1-VDD") (pinfunction "VDD_1-VDD") (pintype "power_in"))
      (node (ref "LED40") (pin "1-VDD") (pinfunction "VDD_1-VDD") (pintype "power_in"))
      (node (ref "LED41") (pin "1-VDD") (pinfunction "VDD_1-VDD") (pintype "power_in"))
      (node (ref "LED42") (pin "1-VDD") (pinfunction "VDD_1-VDD") (pintype "power_in"))
      (node (ref "LED43") (pin "1-VDD") (pinfunction "VDD_1-VDD") (pintype "power_in"))
      (node (ref "LED44") (pin "1-VDD") (pinfunction "VDD_1-VDD") (pintype "power_in"))
      (node (ref "LED45") (pin "1-VDD") (pinfunction "VDD_1-VDD") (pintype "power_in"))
      (node (ref "LED46") (pin "1-VDD") (pinfunction "VDD_1-VDD") (pintype "power_in"))
      (node (ref "LED47") (pin "1-VDD") (pinfunction "VDD_1-VDD") (pintype "power_in"))
      (node (ref "LED48") (pin "1-VDD") (pinfunction "VDD_1-VDD") (pintype "power_in"))
      (node (ref "LED49") (pin "1-VDD") (pinfunction "VDD_1-VDD") (pintype "power_in"))
      (node (ref "LED5") (pin "1-VDD") (pinfunction "VDD_1-VDD") (pintype "power_in"))
      (node (ref "LED50") (pin "1-VDD") (pinfunction "VDD_1-VDD") (pintype "power_in"))
      (node (ref "LED51") (pin "1-VDD") (pinfunction "VDD_1-VDD") (pintype "power_in"))
      (node (ref "LED52") (pin "1-VDD") (pinfunction "VDD_1-VDD") (pintype "power_in"))
      (node (ref "LED53") (pin "1-VDD") (pinfunction "VDD_1-VDD") (pintype "power_in"))
      (node (ref "LED54") (pin "1-VDD") (pinfunction "VDD_1-VDD") (pintype "power_in"))
      (node (ref "LED55") (pin "1-VDD") (pinfunction "VDD_1-VDD") (pintype "power_in"))
      (node (ref "LED56") (pin "1-VDD") (pinfunction "VDD_1-VDD") (pintype "power_in"))
      (node (ref "LED57") (pin "1-VDD") (pinfunction "VDD_1-VDD") (pintype "power_in"))
      (node (ref "LED58") (pin "1-VDD") (pinfunction "VDD_1-VDD") (pintype "power_in"))
      (node (ref "LED59") (pin "1-VDD") (pinfunction "VDD_1-VDD") (pintype "power_in"))
      (node (ref "LED6") (pin "1-VDD") (pinfunction "VDD_1-VDD") (pintype "power_in"))
      (node (ref "LED60") (pin "1-VDD") (pinfunction "VDD_1-VDD") (pintype "power_in"))
      (node (ref "LED61") (pin "1-VDD") (pinfunction "VDD_1-VDD") (pintype "power_in"))
      (node (ref "LED7") (pin "1-VDD") (pinfunction "VDD_1-VDD") (pintype "power_in"))
      (node (ref "LED8") (pin "1-VDD") (pinfunction "VDD_1-VDD") (pintype "power_in"))
      (node (ref "LED9") (pin "1-VDD") (pinfunction "VDD_1-VDD") (pintype "power_in"))
      (node (ref "LEDS") (pin "3") (pinfunction "3_3") (pintype "passive"))
      (node (ref "U$3") (pin "VCC") (pinfunction "VCC_VCC") (pintype "bidirectional"))
      (node (ref "U1") (pin "VCC") (pinfunction "VCC_VCC") (pintype "bidirectional"))
    )
    (net (code "64") (name "unconnected-(GYRO-PadDRDY)") (class "Default")
      (node (ref "GYRO") (pin "DRDY") (pinfunction "DRDY_DRDY") (pintype "bidirectional"))
    )
    (net (code "65") (name "unconnected-(LED1-DI-Pad4-DIN)") (class "Default")
      (node (ref "LED1") (pin "4-DIN") (pinfunction "DI_4-DIN") (pintype "input"))
    )
    (net (code "66") (name "unconnected-(LED10-DO-Pad2-DOUT)") (class "Default")
      (node (ref "LED10") (pin "2-DOUT") (pinfunction "DO_2-DOUT") (pintype "output"))
    )
    (net (code "67") (name "unconnected-(LED11-DI-Pad4-DIN)") (class "Default")
      (node (ref "LED11") (pin "4-DIN") (pinfunction "DI_4-DIN") (pintype "input"))
    )
    (net (code "68") (name "unconnected-(LED20-DO-Pad2-DOUT)") (class "Default")
      (node (ref "LED20") (pin "2-DOUT") (pinfunction "DO_2-DOUT") (pintype "output"))
    )
    (net (code "69") (name "unconnected-(LED21-DI-Pad4-DIN)") (class "Default")
      (node (ref "LED21") (pin "4-DIN") (pinfunction "DI_4-DIN") (pintype "input"))
    )
    (net (code "70") (name "unconnected-(LED30-DO-Pad2-DOUT)") (class "Default")
      (node (ref "LED30") (pin "2-DOUT") (pinfunction "DO_2-DOUT") (pintype "output"))
    )
    (net (code "71") (name "unconnected-(LED31-DI-Pad4-DIN)") (class "Default")
      (node (ref "LED31") (pin "4-DIN") (pinfunction "DI_4-DIN") (pintype "input"))
    )
    (net (code "72") (name "unconnected-(LED40-DO-Pad2-DOUT)") (class "Default")
      (node (ref "LED40") (pin "2-DOUT") (pinfunction "DO_2-DOUT") (pintype "output"))
    )
    (net (code "73") (name "unconnected-(LED41-DI-Pad4-DIN)") (class "Default")
      (node (ref "LED41") (pin "4-DIN") (pinfunction "DI_4-DIN") (pintype "input"))
    )
    (net (code "74") (name "unconnected-(LED50-DO-Pad2-DOUT)") (class "Default")
      (node (ref "LED50") (pin "2-DOUT") (pinfunction "DO_2-DOUT") (pintype "output"))
    )
    (net (code "75") (name "unconnected-(LED51-DI-Pad4-DIN)") (class "Default")
      (node (ref "LED51") (pin "4-DIN") (pinfunction "DI_4-DIN") (pintype "input"))
    )
    (net (code "76") (name "unconnected-(LED61-DO-Pad2-DOUT)") (class "Default")
      (node (ref "LED61") (pin "2-DOUT") (pinfunction "DO_2-DOUT") (pintype "output"))
    )
    (net (code "77") (name "unconnected-(U1-*GPIO9-PadGPIO9)") (class "Default")
      (node (ref "U1") (pin "GPIO9") (pinfunction "*GPIO9_GPIO9") (pintype "bidirectional"))
    )
    (net (code "78") (name "unconnected-(U1-*GPIO10-PadGPIO10)") (class "Default")
      (node (ref "U1") (pin "GPIO10") (pinfunction "*GPIO10_GPIO10") (pintype "bidirectional"))
    )
    (net (code "79") (name "unconnected-(U1-PadADC)") (class "Default")
      (node (ref "U1") (pin "ADC") (pinfunction "ADC_ADC") (pintype "bidirectional"))
    )
    (net (code "80") (name "unconnected-(U1-PadCH_PD)") (class "Default")
      (node (ref "U1") (pin "CH_PD") (pinfunction "CH_PD_CH_PD") (pintype "bidirectional"))
    )
    (net (code "81") (name "unconnected-(U1-PadCS0)") (class "Default")
      (node (ref "U1") (pin "CS0") (pinfunction "CS0_CS0") (pintype "bidirectional"))
    )
    (net (code "82") (name "unconnected-(U1-PadGPIO0)") (class "Default")
      (node (ref "U1") (pin "GPIO0") (pinfunction "GPIO0_GPIO0") (pintype "bidirectional"))
    )
    (net (code "83") (name "unconnected-(U1-PadGPIO2)") (class "Default")
      (node (ref "U1") (pin "GPIO2") (pinfunction "GPIO2_GPIO2") (pintype "bidirectional"))
    )
    (net (code "84") (name "unconnected-(U1-PadGPIO12)") (class "Default")
      (node (ref "U1") (pin "GPIO12") (pinfunction "GPIO12_GPIO12") (pintype "bidirectional"))
    )
    (net (code "85") (name "unconnected-(U1-PadGPIO13)") (class "Default")
      (node (ref "U1") (pin "GPIO13") (pinfunction "GPIO13_GPIO13") (pintype "bidirectional"))
    )
    (net (code "86") (name "unconnected-(U1-PadGPIO14)") (class "Default")
      (node (ref "U1") (pin "GPIO14") (pinfunction "GPIO14_GPIO14") (pintype "bidirectional"))
    )
    (net (code "87") (name "unconnected-(U1-PadGPIO15)") (class "Default")
      (node (ref "U1") (pin "GPIO15") (pinfunction "GPIO15_GPIO15") (pintype "bidirectional"))
    )
    (net (code "88") (name "unconnected-(U1-PadGPIO16)") (class "Default")
      (node (ref "U1") (pin "GPIO16") (pinfunction "GPIO16_GPIO16") (pintype "bidirectional"))
    )
    (net (code "89") (name "unconnected-(U1-PadMISO)") (class "Default")
      (node (ref "U1") (pin "MISO") (pinfunction "MISO_MISO") (pintype "bidirectional"))
    )
    (net (code "90") (name "unconnected-(U1-PadMOSI)") (class "Default")
      (node (ref "U1") (pin "MOSI") (pinfunction "MOSI_MOSI") (pintype "bidirectional"))
    )
    (net (code "91") (name "unconnected-(U1-PadRESET)") (class "Default")
      (node (ref "U1") (pin "RESET") (pinfunction "RESET_RESET") (pintype "bidirectional"))
    )
    (net (code "92") (name "unconnected-(U1-PadSCLK)") (class "Default")
      (node (ref "U1") (pin "SCLK") (pinfunction "SCLK_SCLK") (pintype "bidirectional"))
    )
  )
)
